# pwr-driver.net
KiCad netlist of a schematic drawn in EAGLE
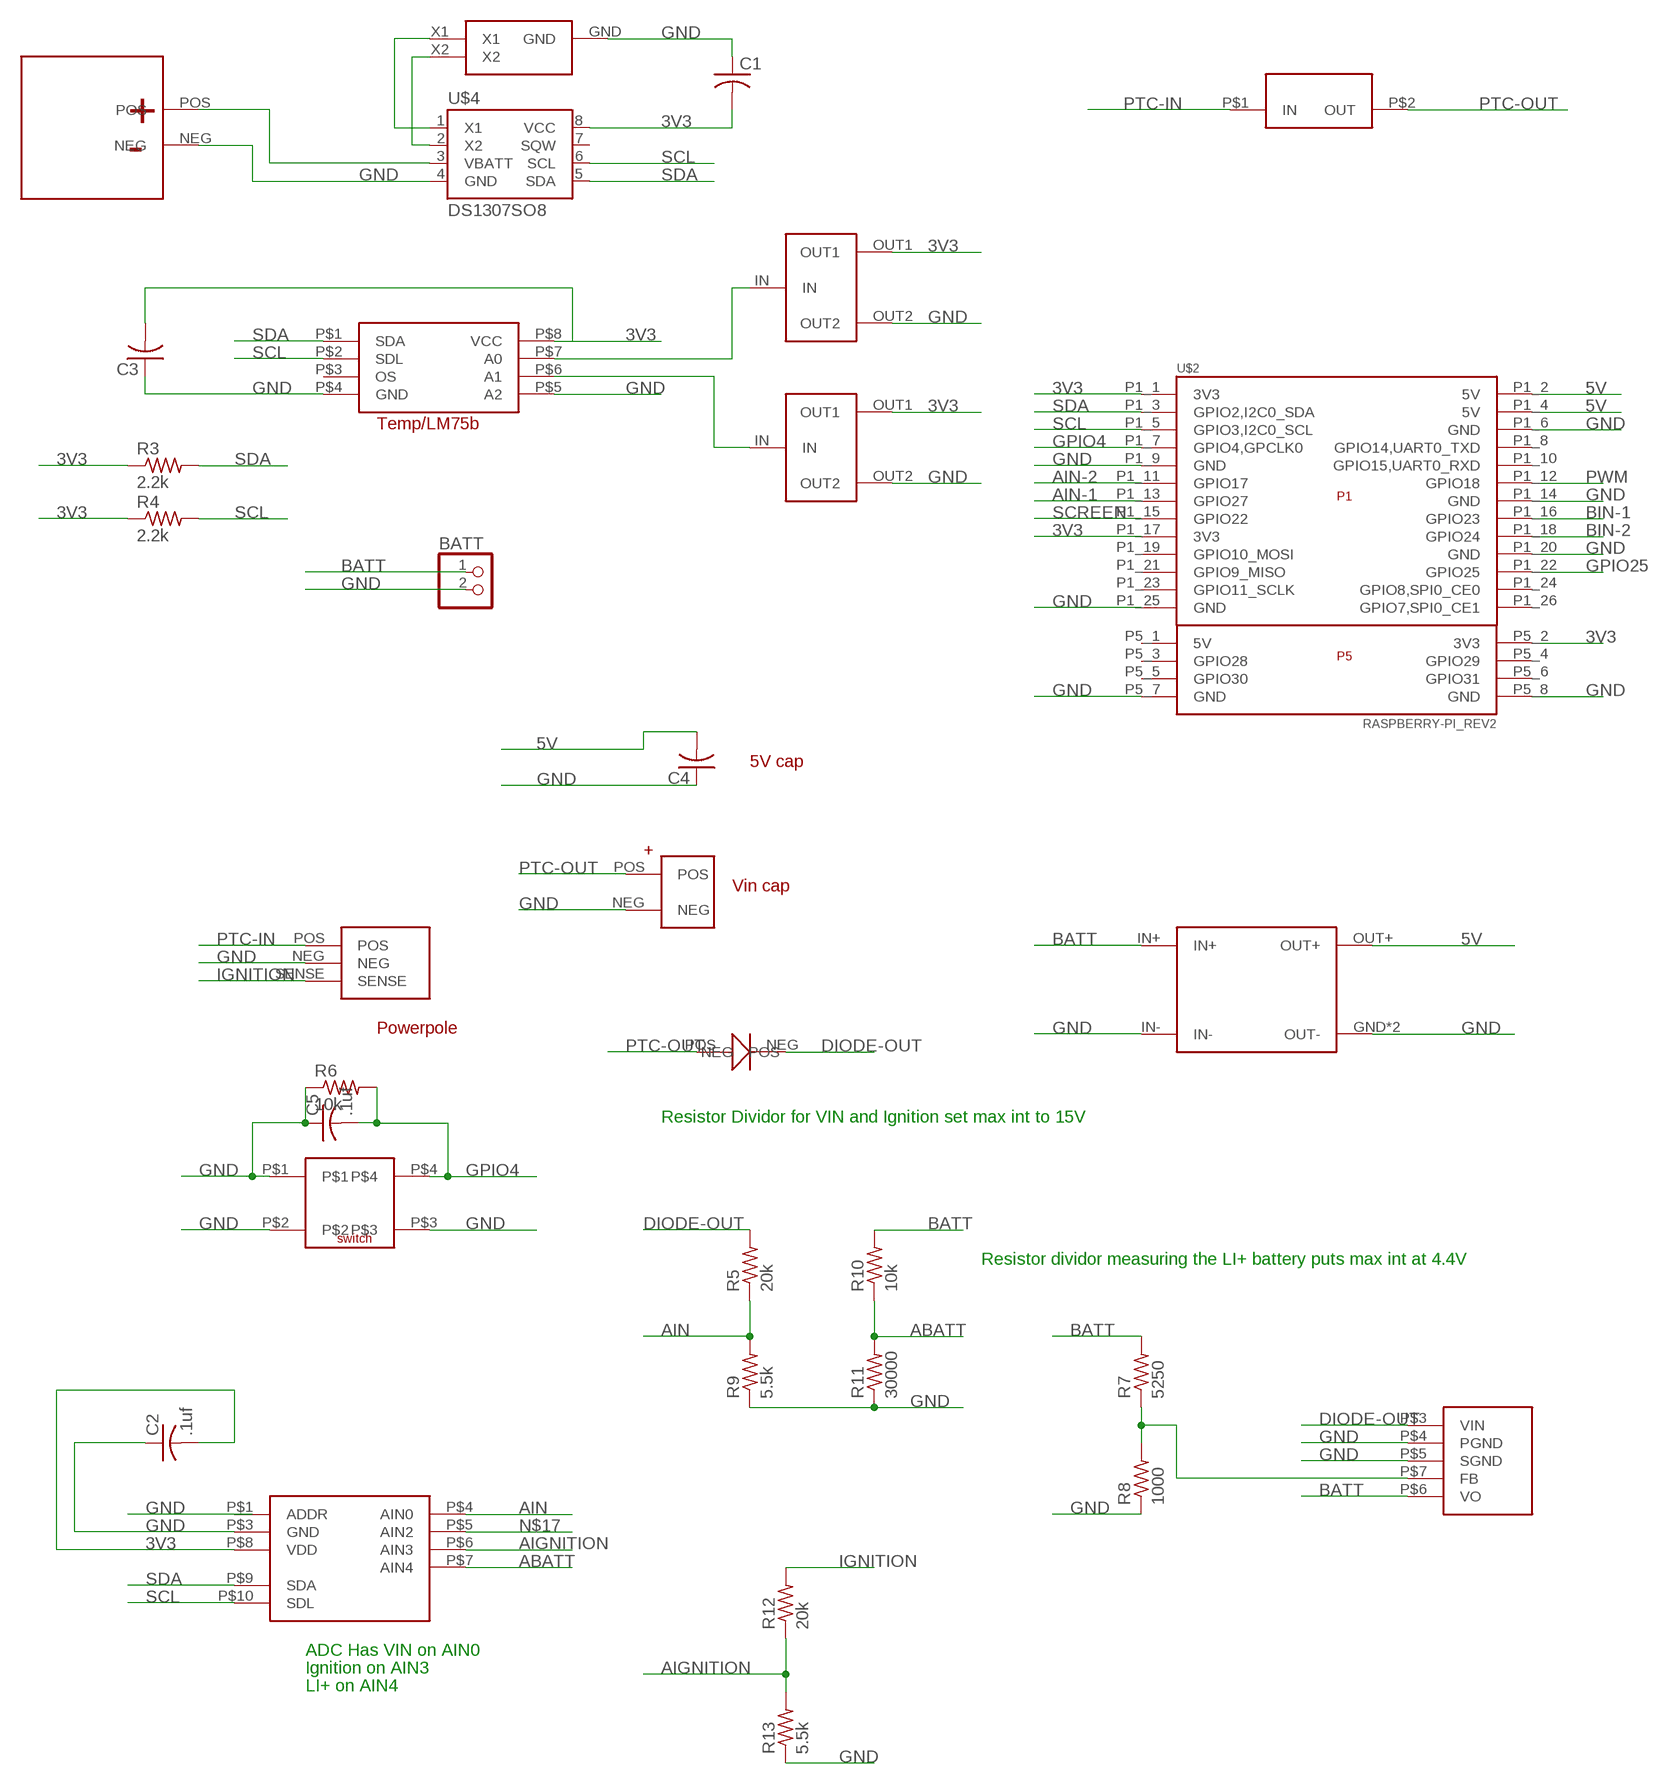
[diagram p0: schematic, sheet 1]

(export (version "E")
  (design (tool "Eeschema 10.0.6"))
  (components
    (comp (ref "BATT")
      (value "PINHD-1X2")
      (footprint "eagle-import:1X02")
      (libsource (lib "eagle-import") (part "PINHD-1X2"))
    )
    (comp (ref "C1")
      (value "C-USC0805K")
      (footprint "eagle-import:C0805K")
      (libsource (lib "eagle-import") (part "C-USC0805K"))
    )
    (comp (ref "C2")
      (value ".1uf")
      (footprint "eagle-import:C0603")
      (libsource (lib "eagle-import") (part "C-USC0603"))
    )
    (comp (ref "C3")
      (value "C-USC0805")
      (footprint "eagle-import:C0805")
      (libsource (lib "eagle-import") (part "C-USC0805"))
    )
    (comp (ref "C4")
      (value "C-USC3216")
      (footprint "eagle-import:C3216")
      (libsource (lib "eagle-import") (part "C-USC3216"))
    )
    (comp (ref "C5")
      (value ".1uf")
      (footprint "eagle-import:C0603")
      (libsource (lib "eagle-import") (part "C-USC0603"))
    )
    (comp (ref "R3")
      (value "2.2k")
      (footprint "eagle-import:R0603")
      (libsource (lib "eagle-import") (part "R-US_R0603"))
    )
    (comp (ref "R4")
      (value "2.2k")
      (footprint "eagle-import:R0603")
      (libsource (lib "eagle-import") (part "R-US_R0603"))
    )
    (comp (ref "R5")
      (value "20k")
      (footprint "eagle-import:R0603")
      (libsource (lib "eagle-import") (part "R-US_R0603"))
    )
    (comp (ref "R6")
      (value "10k")
      (footprint "eagle-import:R0603")
      (libsource (lib "eagle-import") (part "R-US_R0603"))
    )
    (comp (ref "R7")
      (value "5250")
      (footprint "eagle-import:R0603")
      (libsource (lib "eagle-import") (part "R-US_R0603"))
    )
    (comp (ref "R8")
      (value "1000")
      (footprint "eagle-import:R0603")
      (libsource (lib "eagle-import") (part "R-US_R0603"))
    )
    (comp (ref "R9")
      (value "5.5k")
      (footprint "eagle-import:R0603")
      (libsource (lib "eagle-import") (part "R-US_R0603"))
    )
    (comp (ref "R10")
      (value "10k")
      (footprint "eagle-import:R0603")
      (libsource (lib "eagle-import") (part "R-US_R0603"))
    )
    (comp (ref "R11")
      (value "30000")
      (footprint "eagle-import:R0603")
      (libsource (lib "eagle-import") (part "R-US_R0603"))
    )
    (comp (ref "R12")
      (value "20k")
      (footprint "eagle-import:R0603")
      (libsource (lib "eagle-import") (part "R-US_R0603"))
    )
    (comp (ref "R13")
      (value "5.5k")
      (footprint "eagle-import:R0603")
      (libsource (lib "eagle-import") (part "R-US_R0603"))
    )
    (comp (ref "U$1")
      (value "MPM80")
      (footprint "eagle-import:TO-220-8L")
      (libsource (lib "eagle-import") (part "MPM80"))
    )
    (comp (ref "U$2")
      (value "RASPBERRY-PI_REV2")
      (footprint "eagle-import:RASPBERRY-PI_REV2")
      (libsource (lib "eagle-import") (part "RASPBERRY-PI_REV2"))
    )
    (comp (ref "U$3")
      (value "STEP-UP-FROM-AMAZON")
      (footprint "eagle-import:STEP-UP-FROM-AMAZON")
      (libsource (lib "eagle-import") (part "STEP-UP-FROM-AMAZON"))
    )
    (comp (ref "U$4")
      (value "DS1307SO8")
      (footprint "eagle-import:SO08")
      (libsource (lib "eagle-import") (part "DS1307SO8"))
    )
    (comp (ref "U$5")
      (value "BATTERY-MS518SE")
      (footprint "eagle-import:BATTERY-MS518SE-FL35E")
      (libsource (lib "eagle-import") (part "BATTERY-MS518SE"))
    )
    (comp (ref "U$6")
      (value "AB26T-CRYSTAL")
      (footprint "eagle-import:AB26T-CRYSTAL")
      (libsource (lib "eagle-import") (part "AB26T-CRYSTAL"))
    )
    (comp (ref "U$7")
      (value "POWERPOLE-WITH-SENSE")
      (footprint "eagle-import:POWERPOLE-3")
      (libsource (lib "eagle-import") (part "POWERPOLE-WITH-SENSE"))
    )
    (comp (ref "U$8")
      (value "PTC")
      (footprint "eagle-import:PTC-0ZRM0100FF1E")
      (libsource (lib "eagle-import") (part "PTC"))
    )
    (comp (ref "U$9")
      (value "LM75-BDP-TEMP")
      (footprint "eagle-import:TSSOP8")
      (libsource (lib "eagle-import") (part "LM75-BDP-TEMP"))
    )
    (comp (ref "U$10")
      (value "ADS1013")
      (footprint "eagle-import:MSOP-10")
      (libsource (lib "eagle-import") (part "ADS1013"))
    )
    (comp (ref "U$11")
      (value "CAP-SMD-100U")
      (footprint "eagle-import:CAP-100UF-SMD")
      (libsource (lib "eagle-import") (part "CAP-SMD-100U"))
    )
    (comp (ref "U$12")
      (value "0805-3-WAY")
      (footprint "eagle-import:0805-3-WAY")
      (libsource (lib "eagle-import") (part "0805-3-WAY"))
    )
    (comp (ref "U$13")
      (value "0805-3-WAY")
      (footprint "eagle-import:0805-3-WAY")
      (libsource (lib "eagle-import") (part "0805-3-WAY"))
    )
    (comp (ref "U$14")
      (value "MICRO-SWITCH")
      (footprint "eagle-import:BUTTON-MICRO-SWITCH")
      (libsource (lib "eagle-import") (part "MICRO-SWITCH"))
    )
    (comp (ref "U$15")
      (value "DIODE-403")
      (footprint "eagle-import:403")
      (libsource (lib "eagle-import") (part "DIODE-403"))
    )
  )
  (nets
    (net (code "1") (name "/3V3") (class "Default")
      (node (ref "C1") (pin "2") (pinfunction "2_2") (pintype "passive"))
      (node (ref "C2") (pin "2") (pinfunction "2_2") (pintype "passive"))
      (node (ref "C3") (pin "2") (pinfunction "2_2") (pintype "passive"))
      (node (ref "R3") (pin "1") (pinfunction "1_1") (pintype "passive"))
      (node (ref "R4") (pin "1") (pinfunction "1_1") (pintype "passive"))
      (node (ref "U$10") (pin "P$8") (pinfunction "VDD_P$8") (pintype "bidirectional"))
      (node (ref "U$12") (pin "OUT1") (pinfunction "OUT1_OUT1") (pintype "bidirectional"))
      (node (ref "U$13") (pin "OUT1") (pinfunction "OUT1_OUT1") (pintype "bidirectional"))
      (node (ref "U$2") (pin "P1_1") (pinfunction "3V3_P1_1") (pintype "bidirectional"))
      (node (ref "U$2") (pin "P1_17") (pinfunction "3V3_P1_17") (pintype "bidirectional"))
      (node (ref "U$2") (pin "P5_2") (pinfunction "3V3_P5_2") (pintype "bidirectional"))
      (node (ref "U$4") (pin "8") (pinfunction "VCC_8") (pintype "bidirectional"))
      (node (ref "U$9") (pin "P$8") (pinfunction "VCC_P$8") (pintype "bidirectional"))
    )
    (net (code "2") (name "/5V") (class "Default")
      (node (ref "C4") (pin "2") (pinfunction "2_2") (pintype "passive"))
      (node (ref "U$2") (pin "P1_2") (pinfunction "5V_P1_2") (pintype "bidirectional"))
      (node (ref "U$2") (pin "P1_4") (pinfunction "5V_P1_4") (pintype "bidirectional"))
      (node (ref "U$3") (pin "OUT+") (pinfunction "OUT+_OUT+") (pintype "bidirectional"))
    )
    (net (code "3") (name "/ABATT") (class "Default")
      (node (ref "R10") (pin "1") (pinfunction "1_1") (pintype "passive"))
      (node (ref "R11") (pin "2") (pinfunction "2_2") (pintype "passive"))
      (node (ref "U$10") (pin "P$7") (pinfunction "AIN4_P$7") (pintype "bidirectional"))
    )
    (net (code "4") (name "/AIGNITION") (class "Default")
      (node (ref "R12") (pin "1") (pinfunction "1_1") (pintype "passive"))
      (node (ref "R13") (pin "2") (pinfunction "2_2") (pintype "passive"))
      (node (ref "U$10") (pin "P$6") (pinfunction "AIN3_P$6") (pintype "bidirectional"))
    )
    (net (code "5") (name "/AIN") (class "Default")
      (node (ref "R5") (pin "1") (pinfunction "1_1") (pintype "passive"))
      (node (ref "R9") (pin "2") (pinfunction "2_2") (pintype "passive"))
      (node (ref "U$10") (pin "P$4") (pinfunction "AIN0_P$4") (pintype "bidirectional"))
    )
    (net (code "6") (name "/AIN-1") (class "Default")
      (node (ref "U$2") (pin "P1_13") (pinfunction "GPIO27_P1_13") (pintype "bidirectional"))
    )
    (net (code "7") (name "/AIN-2") (class "Default")
      (node (ref "U$2") (pin "P1_11") (pinfunction "GPIO17_P1_11") (pintype "bidirectional"))
    )
    (net (code "8") (name "/BATT") (class "Default")
      (node (ref "BATT") (pin "1") (pinfunction "1_1") (pintype "passive"))
      (node (ref "R10") (pin "2") (pinfunction "2_2") (pintype "passive"))
      (node (ref "R7") (pin "2") (pinfunction "2_2") (pintype "passive"))
      (node (ref "U$1") (pin "P$6") (pinfunction "VO_P$6") (pintype "bidirectional"))
      (node (ref "U$3") (pin "IN+") (pinfunction "IN+_IN+") (pintype "bidirectional"))
    )
    (net (code "9") (name "/BIN-1") (class "Default")
      (node (ref "U$2") (pin "P1_16") (pinfunction "GPIO23_P1_16") (pintype "bidirectional"))
    )
    (net (code "10") (name "/BIN-2") (class "Default")
      (node (ref "U$2") (pin "P1_18") (pinfunction "GPIO24_P1_18") (pintype "bidirectional"))
    )
    (net (code "11") (name "/DIODE-OUT") (class "Default")
      (node (ref "R5") (pin "2") (pinfunction "2_2") (pintype "passive"))
      (node (ref "U$1") (pin "P$3") (pinfunction "VIN_P$3") (pintype "bidirectional"))
      (node (ref "U$15") (pin "NEG") (pinfunction "NEG_NEG") (pintype "bidirectional"))
    )
    (net (code "12") (name "/GND") (class "Default")
      (node (ref "BATT") (pin "2") (pinfunction "2_2") (pintype "passive"))
      (node (ref "C1") (pin "1") (pinfunction "1_1") (pintype "passive"))
      (node (ref "C2") (pin "1") (pinfunction "1_1") (pintype "passive"))
      (node (ref "C3") (pin "1") (pinfunction "1_1") (pintype "passive"))
      (node (ref "C4") (pin "1") (pinfunction "1_1") (pintype "passive"))
      (node (ref "C5") (pin "1") (pinfunction "1_1") (pintype "passive"))
      (node (ref "R11") (pin "1") (pinfunction "1_1") (pintype "passive"))
      (node (ref "R13") (pin "1") (pinfunction "1_1") (pintype "passive"))
      (node (ref "R6") (pin "1") (pinfunction "1_1") (pintype "passive"))
      (node (ref "R8") (pin "1") (pinfunction "1_1") (pintype "passive"))
      (node (ref "R9") (pin "1") (pinfunction "1_1") (pintype "passive"))
      (node (ref "U$1") (pin "P$4") (pinfunction "PGND_P$4") (pintype "bidirectional"))
      (node (ref "U$1") (pin "P$5") (pinfunction "SGND_P$5") (pintype "bidirectional"))
      (node (ref "U$10") (pin "P$3") (pinfunction "GND_P$3") (pintype "bidirectional"))
      (node (ref "U$11") (pin "NEG") (pinfunction "NEG_NEG") (pintype "bidirectional"))
      (node (ref "U$12") (pin "OUT2") (pinfunction "OUT2_OUT2") (pintype "bidirectional"))
      (node (ref "U$13") (pin "OUT2") (pinfunction "OUT2_OUT2") (pintype "bidirectional"))
      (node (ref "U$14") (pin "P$1") (pinfunction "P$1_P$1") (pintype "bidirectional"))
      (node (ref "U$14") (pin "P$2") (pinfunction "P$2_P$2") (pintype "bidirectional"))
      (node (ref "U$14") (pin "P$3") (pinfunction "P$3_P$3") (pintype "bidirectional"))
      (node (ref "U$2") (pin "P1_14") (pinfunction "GND_P1_14") (pintype "bidirectional"))
      (node (ref "U$2") (pin "P1_20") (pinfunction "GND_P1_20") (pintype "bidirectional"))
      (node (ref "U$2") (pin "P1_25") (pinfunction "GND_P1_25") (pintype "bidirectional"))
      (node (ref "U$2") (pin "P1_6") (pinfunction "GND_P1_6") (pintype "bidirectional"))
      (node (ref "U$2") (pin "P1_9") (pinfunction "GND_P1_9") (pintype "bidirectional"))
      (node (ref "U$2") (pin "P5_7") (pinfunction "GND_P5_7") (pintype "bidirectional"))
      (node (ref "U$2") (pin "P5_8") (pinfunction "GND_P5_8") (pintype "bidirectional"))
      (node (ref "U$3") (pin "GND") (pinfunction "OUT-_GND") (pintype "bidirectional"))
      (node (ref "U$3") (pin "IN-") (pinfunction "IN-_IN-") (pintype "bidirectional"))
      (node (ref "U$3") (pin "OUT-") (pinfunction "OUT-_OUT-") (pintype "bidirectional"))
      (node (ref "U$4") (pin "4") (pinfunction "GND_4") (pintype "bidirectional"))
      (node (ref "U$5") (pin "NEG") (pinfunction "NEG_NEG") (pintype "bidirectional"))
      (node (ref "U$6") (pin "GND") (pinfunction "GND_GND") (pintype "bidirectional"))
      (node (ref "U$7") (pin "NEG") (pinfunction "NEG_NEG") (pintype "bidirectional"))
      (node (ref "U$9") (pin "P$4") (pinfunction "GND_P$4") (pintype "bidirectional"))
      (node (ref "U$9") (pin "P$5") (pinfunction "A2_P$5") (pintype "bidirectional"))
    )
    (net (code "13") (name "/GPIO4") (class "Default")
      (node (ref "C5") (pin "2") (pinfunction "2_2") (pintype "passive"))
      (node (ref "R6") (pin "2") (pinfunction "2_2") (pintype "passive"))
      (node (ref "U$14") (pin "P$4") (pinfunction "P$4_P$4") (pintype "bidirectional"))
      (node (ref "U$2") (pin "P1_7") (pinfunction "GPIO4,GPCLK0_P1_7") (pintype "bidirectional"))
    )
    (net (code "14") (name "/GPIO25") (class "Default")
      (node (ref "U$2") (pin "P1_22") (pinfunction "GPIO25_P1_22") (pintype "bidirectional"))
    )
    (net (code "15") (name "/IGNITION") (class "Default")
      (node (ref "R12") (pin "2") (pinfunction "2_2") (pintype "passive"))
      (node (ref "U$7") (pin "SENSE") (pinfunction "SENSE_SENSE") (pintype "bidirectional"))
    )
    (net (code "16") (name "/N$17") (class "Default")
      (node (ref "U$10") (pin "P$5") (pinfunction "AIN2_P$5") (pintype "bidirectional"))
    )
    (net (code "17") (name "/PTC-IN") (class "Default")
      (node (ref "U$7") (pin "POS") (pinfunction "POS_POS") (pintype "bidirectional"))
      (node (ref "U$8") (pin "P$1") (pinfunction "IN_P$1") (pintype "bidirectional"))
    )
    (net (code "18") (name "/PTC-OUT") (class "Default")
      (node (ref "U$11") (pin "POS") (pinfunction "POS_POS") (pintype "bidirectional"))
      (node (ref "U$15") (pin "POS") (pinfunction "POS_POS") (pintype "bidirectional"))
      (node (ref "U$8") (pin "P$2") (pinfunction "OUT_P$2") (pintype "bidirectional"))
    )
    (net (code "19") (name "/PWM") (class "Default")
      (node (ref "U$2") (pin "P1_12") (pinfunction "GPIO18_P1_12") (pintype "bidirectional"))
    )
    (net (code "20") (name "/SCL") (class "Default")
      (node (ref "R4") (pin "2") (pinfunction "2_2") (pintype "passive"))
      (node (ref "U$10") (pin "P$10") (pinfunction "SDL_P$10") (pintype "bidirectional"))
      (node (ref "U$2") (pin "P1_5") (pinfunction "GPIO3,I2C0_SCL_P1_5") (pintype "bidirectional"))
      (node (ref "U$4") (pin "6") (pinfunction "SCL_6") (pintype "bidirectional"))
      (node (ref "U$9") (pin "P$2") (pinfunction "SDL_P$2") (pintype "bidirectional"))
    )
    (net (code "21") (name "/SCREEN") (class "Default")
      (node (ref "U$2") (pin "P1_15") (pinfunction "GPIO22_P1_15") (pintype "bidirectional"))
    )
    (net (code "22") (name "/SDA") (class "Default")
      (node (ref "R3") (pin "2") (pinfunction "2_2") (pintype "passive"))
      (node (ref "U$10") (pin "P$9") (pinfunction "SDA_P$9") (pintype "bidirectional"))
      (node (ref "U$2") (pin "P1_3") (pinfunction "GPIO2,I2C0_SDA_P1_3") (pintype "bidirectional"))
      (node (ref "U$4") (pin "5") (pinfunction "SDA_5") (pintype "bidirectional"))
      (node (ref "U$9") (pin "P$1") (pinfunction "SDA_P$1") (pintype "bidirectional"))
    )
    (net (code "23") (name "Net-(U$1-FB)") (class "Default")
      (node (ref "R7") (pin "1") (pinfunction "1_1") (pintype "passive"))
      (node (ref "R8") (pin "2") (pinfunction "2_2") (pintype "passive"))
      (node (ref "U$1") (pin "P$7") (pinfunction "FB_P$7") (pintype "bidirectional"))
    )
    (net (code "24") (name "Net-(U$4-VBATT)") (class "Default")
      (node (ref "U$4") (pin "3") (pinfunction "VBATT_3") (pintype "bidirectional"))
      (node (ref "U$5") (pin "POS") (pinfunction "POS_POS") (pintype "bidirectional"))
    )
    (net (code "25") (name "Net-(U$4-X1)") (class "Default")
      (node (ref "U$4") (pin "1") (pinfunction "X1_1") (pintype "bidirectional"))
      (node (ref "U$6") (pin "X1") (pinfunction "X1_X1") (pintype "bidirectional"))
    )
    (net (code "26") (name "Net-(U$4-X2)") (class "Default")
      (node (ref "U$4") (pin "2") (pinfunction "X2_2") (pintype "bidirectional"))
      (node (ref "U$6") (pin "X2") (pinfunction "X2_X2") (pintype "bidirectional"))
    )
    (net (code "27") (name "Net-(U$9-A0)") (class "Default")
      (node (ref "U$12") (pin "IN") (pinfunction "IN_IN") (pintype "bidirectional"))
      (node (ref "U$9") (pin "P$7") (pinfunction "A0_P$7") (pintype "bidirectional"))
    )
    (net (code "28") (name "Net-(U$9-A1)") (class "Default")
      (node (ref "U$13") (pin "IN") (pinfunction "IN_IN") (pintype "bidirectional"))
      (node (ref "U$9") (pin "P$6") (pinfunction "A1_P$6") (pintype "bidirectional"))
    )
    (net (code "29") (name "unconnected-(U$2-5V-PadP5_1)") (class "Default")
      (node (ref "U$2") (pin "P5_1") (pinfunction "5V_P5_1") (pintype "bidirectional"))
    )
    (net (code "30") (name "unconnected-(U$2-GPIO7,SPI0_CE1-PadP1_26)") (class "Default")
      (node (ref "U$2") (pin "P1_26") (pinfunction "GPIO7,SPI0_CE1_P1_26") (pintype "bidirectional"))
    )
    (net (code "31") (name "unconnected-(U$2-GPIO8,SPI0_CE0-PadP1_24)") (class "Default")
      (node (ref "U$2") (pin "P1_24") (pinfunction "GPIO8,SPI0_CE0_P1_24") (pintype "bidirectional"))
    )
    (net (code "32") (name "unconnected-(U$2-GPIO9_MISO-PadP1_21)") (class "Default")
      (node (ref "U$2") (pin "P1_21") (pinfunction "GPIO9_MISO_P1_21") (pintype "bidirectional"))
    )
    (net (code "33") (name "unconnected-(U$2-GPIO10_MOSI-PadP1_19)") (class "Default")
      (node (ref "U$2") (pin "P1_19") (pinfunction "GPIO10_MOSI_P1_19") (pintype "bidirectional"))
    )
    (net (code "34") (name "unconnected-(U$2-GPIO11_SCLK-PadP1_23)") (class "Default")
      (node (ref "U$2") (pin "P1_23") (pinfunction "GPIO11_SCLK_P1_23") (pintype "bidirectional"))
    )
    (net (code "35") (name "unconnected-(U$2-GPIO14,UART0_TXD-PadP1_8)") (class "Default")
      (node (ref "U$2") (pin "P1_8") (pinfunction "GPIO14,UART0_TXD_P1_8") (pintype "bidirectional"))
    )
    (net (code "36") (name "unconnected-(U$2-GPIO15,UART0_RXD-PadP1_10)") (class "Default")
      (node (ref "U$2") (pin "P1_10") (pinfunction "GPIO15,UART0_RXD_P1_10") (pintype "bidirectional"))
    )
    (net (code "37") (name "unconnected-(U$2-GPIO28-PadP5_3)") (class "Default")
      (node (ref "U$2") (pin "P5_3") (pinfunction "GPIO28_P5_3") (pintype "bidirectional"))
    )
    (net (code "38") (name "unconnected-(U$2-GPIO29-PadP5_4)") (class "Default")
      (node (ref "U$2") (pin "P5_4") (pinfunction "GPIO29_P5_4") (pintype "bidirectional"))
    )
    (net (code "39") (name "unconnected-(U$2-GPIO30-PadP5_5)") (class "Default")
      (node (ref "U$2") (pin "P5_5") (pinfunction "GPIO30_P5_5") (pintype "bidirectional"))
    )
    (net (code "40") (name "unconnected-(U$2-GPIO31-PadP5_6)") (class "Default")
      (node (ref "U$2") (pin "P5_6") (pinfunction "GPIO31_P5_6") (pintype "bidirectional"))
    )
    (net (code "41") (name "unconnected-(U$4-SQW-Pad7)") (class "Default")
      (node (ref "U$4") (pin "7") (pinfunction "SQW_7") (pintype "bidirectional"))
    )
    (net (code "42") (name "unconnected-(U$9-OS-PadP$3)") (class "Default")
      (node (ref "U$9") (pin "P$3") (pinfunction "OS_P$3") (pintype "bidirectional"))
    )
    (net (code "43") (name "unconnected-(U$10-ADDR-PadP$1)") (class "Default")
      (node (ref "U$10") (pin "P$1") (pinfunction "ADDR_P$1") (pintype "bidirectional"))
    )
  )
)
